# datalogger.net
KiCad netlist of a schematic drawn in EAGLE
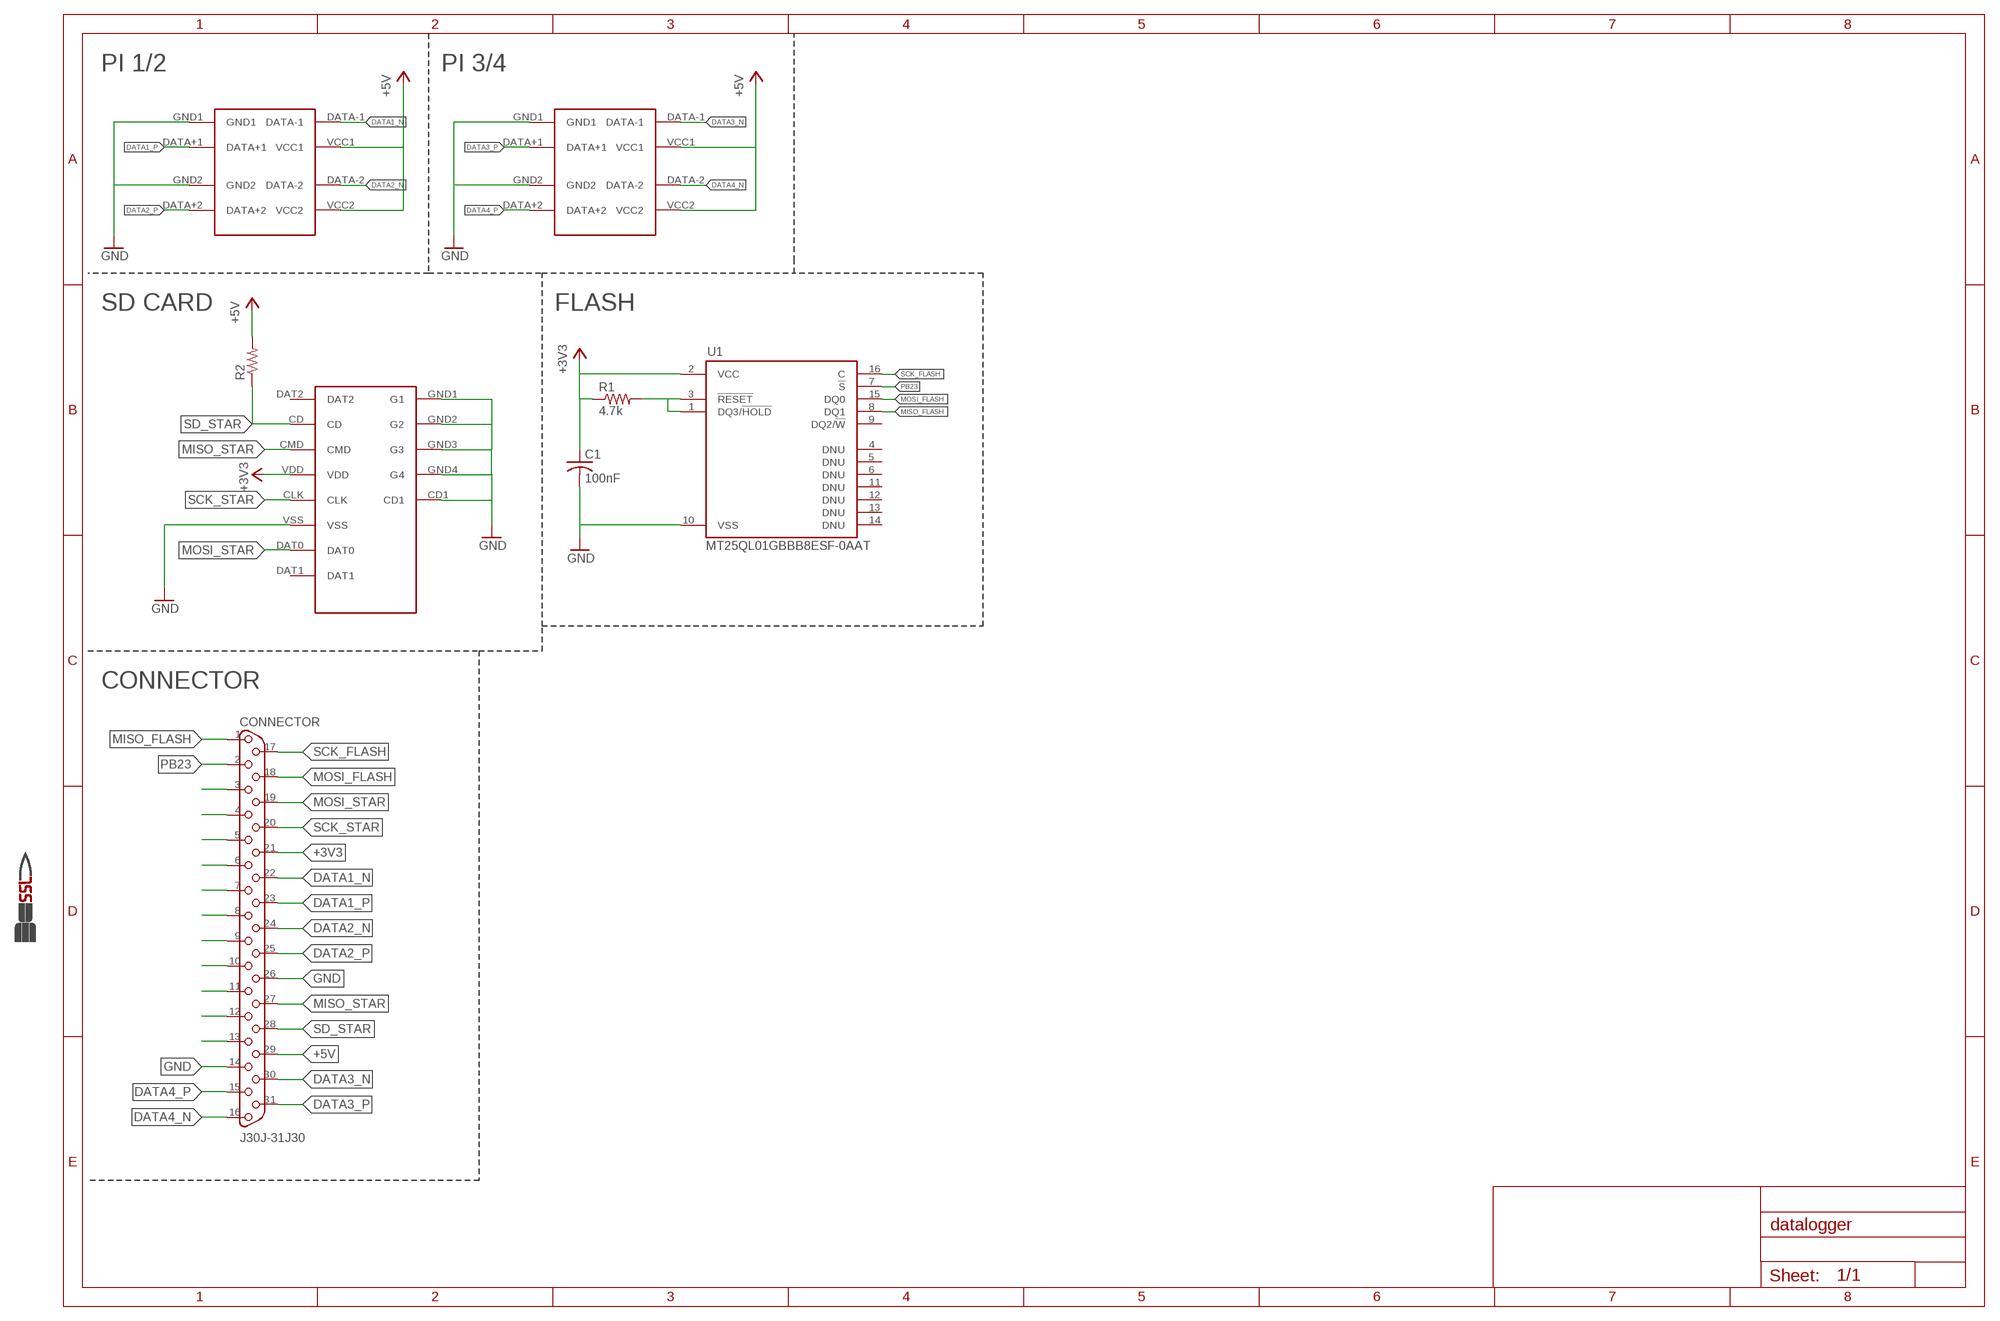
[diagram p0: schematic, sheet 1]

(export (version "E")
  (design (tool "Eeschema 10.0.6"))
  (components
    (comp (ref "C1")
      (value "100nF")
      (footprint "eagle-import:C0603")
      (libsource (lib "eagle-import") (part "C-USC0603"))
    )
    (comp (ref "CONNECTOR")
      (value "J30J-31J30")
      (footprint "eagle-import:ZKN-31-J30")
      (libsource (lib "eagle-import") (part "J30J-31J30"))
    )
    (comp (ref "R1")
      (value "4.7k")
      (footprint "eagle-import:R0603")
      (libsource (lib "eagle-import") (part "R-US_R0603"))
    )
    (comp (ref "R2")
      (value "R-US_R0603")
      (footprint "eagle-import:R0603")
      (libsource (lib "eagle-import") (part "R-US_R0603"))
    )
    (comp (ref "U$1")
      (value "MICRO_SD")
      (footprint "eagle-import:MICRO_SD_HINGED")
      (libsource (lib "eagle-import") (part "MICRO_SD"))
    )
    (comp (ref "U$2")
      (value "USB_A")
      (footprint "eagle-import:USB_A")
      (libsource (lib "eagle-import") (part "USB_A"))
    )
    (comp (ref "U$3")
      (value "USB_A")
      (footprint "eagle-import:USB_A")
      (libsource (lib "eagle-import") (part "USB_A"))
    )
    (comp (ref "U$4")
      (value "SSL.3IN_SILK")
      (footprint "eagle-import:SSL_SILK_.3IN")
      (libsource (lib "eagle-import") (part "SSL.3IN_SILK"))
    )
    (comp (ref "U1")
      (value "MT25QL01GBBB8ESF-0AAT")
      (footprint "eagle-import:SOP2-16")
      (libsource (lib "eagle-import") (part "MT25QL01GBBB8ESF-0AAT"))
    )
  )
  (nets
    (net (code "1") (name "+3V3") (class "Default")
      (node (ref "C1") (pin "1") (pinfunction "1_1") (pintype "passive"))
      (node (ref "CONNECTOR") (pin "21") (pinfunction "21_21") (pintype "bidirectional"))
      (node (ref "R1") (pin "1") (pinfunction "1_1") (pintype "passive"))
      (node (ref "U$1") (pin "VDD") (pinfunction "VDD_VDD") (pintype "bidirectional"))
      (node (ref "U1") (pin "2") (pinfunction "VCC_2") (pintype "bidirectional"))
    )
    (net (code "2") (name "+5V") (class "Default")
      (node (ref "CONNECTOR") (pin "29") (pinfunction "29_29") (pintype "bidirectional"))
      (node (ref "R2") (pin "2") (pinfunction "2_2") (pintype "passive"))
      (node (ref "U$2") (pin "VCC1") (pinfunction "VCC1_VCC1") (pintype "bidirectional"))
      (node (ref "U$2") (pin "VCC2") (pinfunction "VCC2_VCC2") (pintype "bidirectional"))
      (node (ref "U$3") (pin "VCC1") (pinfunction "VCC1_VCC1") (pintype "bidirectional"))
      (node (ref "U$3") (pin "VCC2") (pinfunction "VCC2_VCC2") (pintype "bidirectional"))
    )
    (net (code "3") (name "DATA1_N") (class "Default")
      (node (ref "CONNECTOR") (pin "22") (pinfunction "22_22") (pintype "bidirectional"))
      (node (ref "U$2") (pin "DATA-1") (pinfunction "DATA-1_DATA-1") (pintype "bidirectional"))
    )
    (net (code "4") (name "DATA1_P") (class "Default")
      (node (ref "CONNECTOR") (pin "23") (pinfunction "23_23") (pintype "bidirectional"))
      (node (ref "U$2") (pin "DATA+1") (pinfunction "DATA+1_DATA+1") (pintype "bidirectional"))
    )
    (net (code "5") (name "DATA2_N") (class "Default")
      (node (ref "CONNECTOR") (pin "24") (pinfunction "24_24") (pintype "bidirectional"))
      (node (ref "U$2") (pin "DATA-2") (pinfunction "DATA-2_DATA-2") (pintype "bidirectional"))
    )
    (net (code "6") (name "DATA2_P") (class "Default")
      (node (ref "CONNECTOR") (pin "25") (pinfunction "25_25") (pintype "bidirectional"))
      (node (ref "U$2") (pin "DATA+2") (pinfunction "DATA+2_DATA+2") (pintype "bidirectional"))
    )
    (net (code "7") (name "DATA3_N") (class "Default")
      (node (ref "CONNECTOR") (pin "30") (pinfunction "30_30") (pintype "bidirectional"))
      (node (ref "U$3") (pin "DATA-1") (pinfunction "DATA-1_DATA-1") (pintype "bidirectional"))
    )
    (net (code "8") (name "DATA3_P") (class "Default")
      (node (ref "CONNECTOR") (pin "31") (pinfunction "31_31") (pintype "bidirectional"))
      (node (ref "U$3") (pin "DATA+1") (pinfunction "DATA+1_DATA+1") (pintype "bidirectional"))
    )
    (net (code "9") (name "DATA4_N") (class "Default")
      (node (ref "CONNECTOR") (pin "16") (pinfunction "16_16") (pintype "bidirectional"))
      (node (ref "U$3") (pin "DATA-2") (pinfunction "DATA-2_DATA-2") (pintype "bidirectional"))
    )
    (net (code "10") (name "DATA4_P") (class "Default")
      (node (ref "CONNECTOR") (pin "15") (pinfunction "15_15") (pintype "bidirectional"))
      (node (ref "U$3") (pin "DATA+2") (pinfunction "DATA+2_DATA+2") (pintype "bidirectional"))
    )
    (net (code "11") (name "GND") (class "Default")
      (node (ref "C1") (pin "2") (pinfunction "2_2") (pintype "passive"))
      (node (ref "CONNECTOR") (pin "14") (pinfunction "14_14") (pintype "bidirectional"))
      (node (ref "CONNECTOR") (pin "26") (pinfunction "26_26") (pintype "bidirectional"))
      (node (ref "U$1") (pin "CD1") (pinfunction "CD1_CD1") (pintype "bidirectional"))
      (node (ref "U$1") (pin "GND1") (pinfunction "G1_GND1") (pintype "bidirectional"))
      (node (ref "U$1") (pin "GND2") (pinfunction "G2_GND2") (pintype "bidirectional"))
      (node (ref "U$1") (pin "GND3") (pinfunction "G3_GND3") (pintype "bidirectional"))
      (node (ref "U$1") (pin "GND4") (pinfunction "G4_GND4") (pintype "bidirectional"))
      (node (ref "U$1") (pin "VSS") (pinfunction "VSS_VSS") (pintype "bidirectional"))
      (node (ref "U$2") (pin "GND1") (pinfunction "GND1_GND1") (pintype "bidirectional"))
      (node (ref "U$2") (pin "GND2") (pinfunction "GND2_GND2") (pintype "bidirectional"))
      (node (ref "U$3") (pin "GND1") (pinfunction "GND1_GND1") (pintype "bidirectional"))
      (node (ref "U$3") (pin "GND2") (pinfunction "GND2_GND2") (pintype "bidirectional"))
      (node (ref "U1") (pin "10") (pinfunction "VSS_10") (pintype "bidirectional"))
    )
    (net (code "12") (name "MISO_FLASH") (class "Default")
      (node (ref "CONNECTOR") (pin "1") (pinfunction "1_1") (pintype "bidirectional"))
      (node (ref "U1") (pin "8") (pinfunction "DQ1_8") (pintype "bidirectional"))
    )
    (net (code "13") (name "MISO_STAR") (class "Default")
      (node (ref "CONNECTOR") (pin "27") (pinfunction "27_27") (pintype "bidirectional"))
      (node (ref "U$1") (pin "CMD") (pinfunction "CMD_CMD") (pintype "bidirectional"))
    )
    (net (code "14") (name "MOSI_FLASH") (class "Default")
      (node (ref "CONNECTOR") (pin "18") (pinfunction "18_18") (pintype "bidirectional"))
      (node (ref "U1") (pin "15") (pinfunction "DQ0_15") (pintype "bidirectional"))
    )
    (net (code "15") (name "MOSI_STAR") (class "Default")
      (node (ref "CONNECTOR") (pin "19") (pinfunction "19_19") (pintype "bidirectional"))
      (node (ref "U$1") (pin "DAT0") (pinfunction "DAT0_DAT0") (pintype "bidirectional"))
    )
    (net (code "16") (name "Net-(U1-DQ3{slash}~{HOLD})") (class "Default")
      (node (ref "R1") (pin "2") (pinfunction "2_2") (pintype "passive"))
      (node (ref "U1") (pin "1") (pinfunction "DQ3/~{HOLD}_1") (pintype "bidirectional"))
      (node (ref "U1") (pin "3") (pinfunction "~{RESET}_3") (pintype "bidirectional"))
    )
    (net (code "17") (name "PB23") (class "Default")
      (node (ref "CONNECTOR") (pin "2") (pinfunction "2_2") (pintype "bidirectional"))
      (node (ref "U1") (pin "7") (pinfunction "~{S}_7") (pintype "bidirectional"))
    )
    (net (code "18") (name "SCK_FLASH") (class "Default")
      (node (ref "CONNECTOR") (pin "17") (pinfunction "17_17") (pintype "bidirectional"))
      (node (ref "U1") (pin "16") (pinfunction "C_16") (pintype "bidirectional"))
    )
    (net (code "19") (name "SCK_STAR") (class "Default")
      (node (ref "CONNECTOR") (pin "20") (pinfunction "20_20") (pintype "bidirectional"))
      (node (ref "U$1") (pin "CLK") (pinfunction "CLK_CLK") (pintype "bidirectional"))
    )
    (net (code "20") (name "SD_STAR") (class "Default")
      (node (ref "CONNECTOR") (pin "28") (pinfunction "28_28") (pintype "bidirectional"))
      (node (ref "R2") (pin "1") (pinfunction "1_1") (pintype "passive"))
      (node (ref "U$1") (pin "CD") (pinfunction "CD_CD") (pintype "bidirectional"))
    )
    (net (code "21") (name "unconnected-(CONNECTOR-Pad3)") (class "Default")
      (node (ref "CONNECTOR") (pin "3") (pinfunction "3_3") (pintype "bidirectional"))
    )
    (net (code "22") (name "unconnected-(CONNECTOR-Pad4)") (class "Default")
      (node (ref "CONNECTOR") (pin "4") (pinfunction "4_4") (pintype "bidirectional"))
    )
    (net (code "23") (name "unconnected-(CONNECTOR-Pad5)") (class "Default")
      (node (ref "CONNECTOR") (pin "5") (pinfunction "5_5") (pintype "bidirectional"))
    )
    (net (code "24") (name "unconnected-(CONNECTOR-Pad6)") (class "Default")
      (node (ref "CONNECTOR") (pin "6") (pinfunction "6_6") (pintype "bidirectional"))
    )
    (net (code "25") (name "unconnected-(CONNECTOR-Pad7)") (class "Default")
      (node (ref "CONNECTOR") (pin "7") (pinfunction "7_7") (pintype "bidirectional"))
    )
    (net (code "26") (name "unconnected-(CONNECTOR-Pad8)") (class "Default")
      (node (ref "CONNECTOR") (pin "8") (pinfunction "8_8") (pintype "bidirectional"))
    )
    (net (code "27") (name "unconnected-(CONNECTOR-Pad9)") (class "Default")
      (node (ref "CONNECTOR") (pin "9") (pinfunction "9_9") (pintype "bidirectional"))
    )
    (net (code "28") (name "unconnected-(CONNECTOR-Pad10)") (class "Default")
      (node (ref "CONNECTOR") (pin "10") (pinfunction "10_10") (pintype "bidirectional"))
    )
    (net (code "29") (name "unconnected-(CONNECTOR-Pad11)") (class "Default")
      (node (ref "CONNECTOR") (pin "11") (pinfunction "11_11") (pintype "bidirectional"))
    )
    (net (code "30") (name "unconnected-(CONNECTOR-Pad12)") (class "Default")
      (node (ref "CONNECTOR") (pin "12") (pinfunction "12_12") (pintype "bidirectional"))
    )
    (net (code "31") (name "unconnected-(CONNECTOR-Pad13)") (class "Default")
      (node (ref "CONNECTOR") (pin "13") (pinfunction "13_13") (pintype "bidirectional"))
    )
    (net (code "32") (name "unconnected-(U$1-PadDAT1)") (class "Default")
      (node (ref "U$1") (pin "DAT1") (pinfunction "DAT1_DAT1") (pintype "bidirectional"))
    )
    (net (code "33") (name "unconnected-(U$1-PadDAT2)") (class "Default")
      (node (ref "U$1") (pin "DAT2") (pinfunction "DAT2_DAT2") (pintype "bidirectional"))
    )
    (net (code "34") (name "unconnected-(U1-DNU-Pad4)") (class "Default")
      (node (ref "U1") (pin "4") (pinfunction "DNU_4") (pintype "bidirectional"))
    )
    (net (code "35") (name "unconnected-(U1-DNU-Pad5)") (class "Default")
      (node (ref "U1") (pin "5") (pinfunction "DNU_5") (pintype "bidirectional"))
    )
    (net (code "36") (name "unconnected-(U1-DNU-Pad6)") (class "Default")
      (node (ref "U1") (pin "6") (pinfunction "DNU_6") (pintype "bidirectional"))
    )
    (net (code "37") (name "unconnected-(U1-DNU-Pad11)") (class "Default")
      (node (ref "U1") (pin "11") (pinfunction "DNU_11") (pintype "bidirectional"))
    )
    (net (code "38") (name "unconnected-(U1-DNU-Pad12)") (class "Default")
      (node (ref "U1") (pin "12") (pinfunction "DNU_12") (pintype "bidirectional"))
    )
    (net (code "39") (name "unconnected-(U1-DNU-Pad13)") (class "Default")
      (node (ref "U1") (pin "13") (pinfunction "DNU_13") (pintype "bidirectional"))
    )
    (net (code "40") (name "unconnected-(U1-DNU-Pad14)") (class "Default")
      (node (ref "U1") (pin "14") (pinfunction "DNU_14") (pintype "bidirectional"))
    )
    (net (code "41") (name "unconnected-(U1-DQ2{slash}~{W}-Pad9)") (class "Default")
      (node (ref "U1") (pin "9") (pinfunction "DQ2/~{W}_9") (pintype "bidirectional"))
    )
  )
)
